# design.net
KiCad netlist of a schematic drawn in Altium Designer
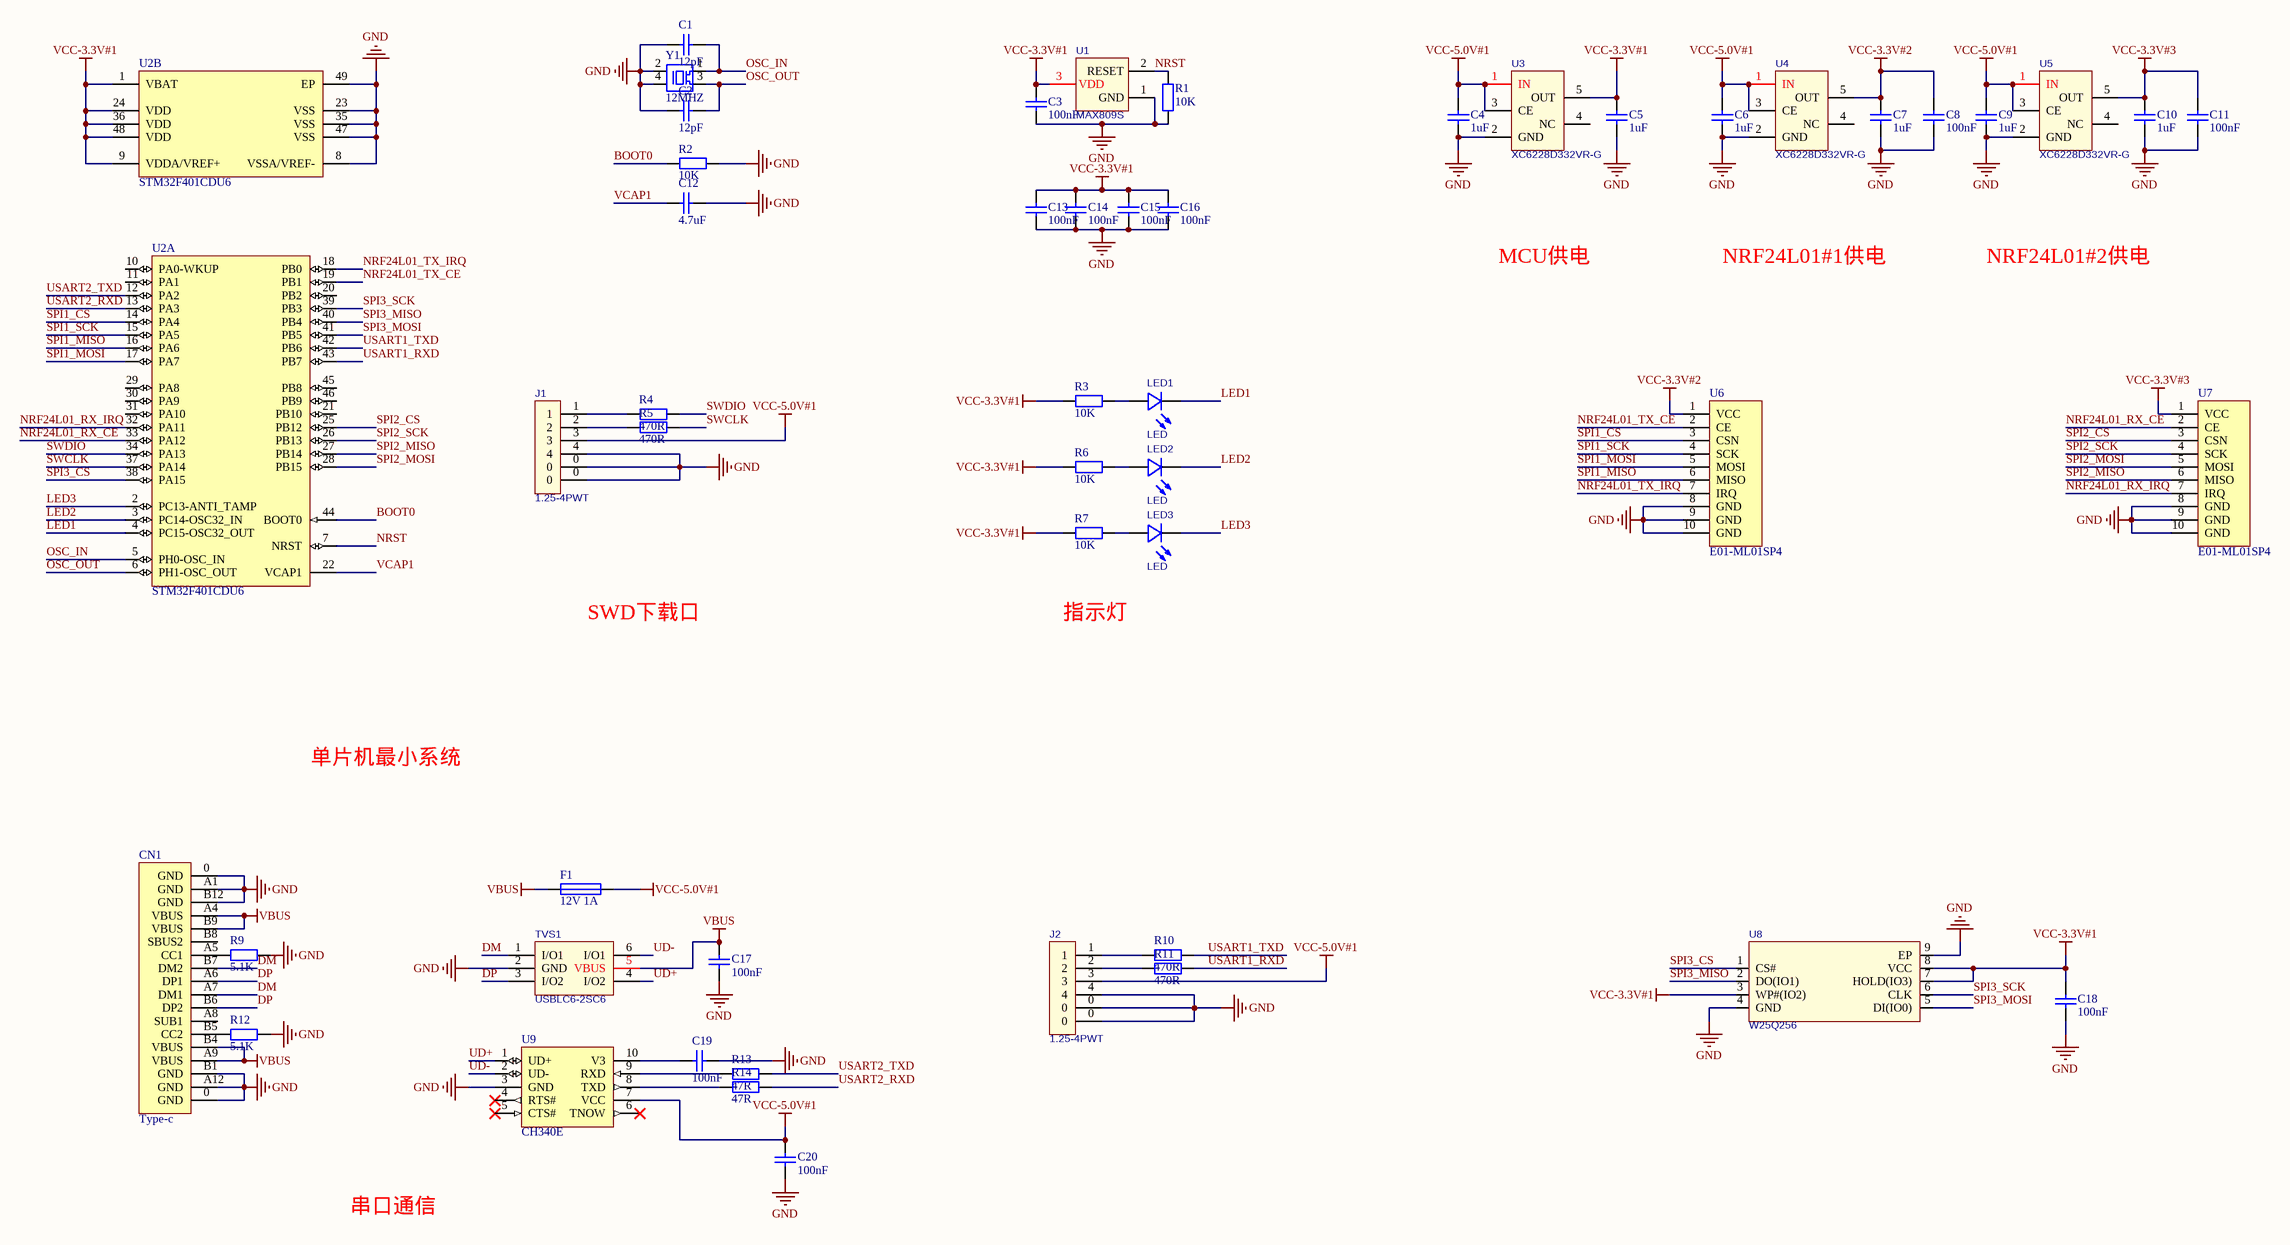
[diagram p0: 数传模块.SchDoc]

(export (version "E")
  (design (tool "Eeschema 10.0.6"))
  (components
    (comp (ref "C1")
      (value "12pF")
      (footprint "0603-C")
      (description "贴片电容")
      (libsource (lib "封装库") (part "C"))
    )
    (comp (ref "C2")
      (value "12pF")
      (footprint "0603-C")
      (description "贴片电容")
      (libsource (lib "封装库") (part "C"))
    )
    (comp (ref "C3")
      (value "100nF")
      (footprint "0603-C")
      (description "贴片电容")
      (libsource (lib "封装库") (part "C"))
    )
    (comp (ref "C4")
      (value "1uF")
      (footprint "0603-C")
      (description "贴片电容")
      (libsource (lib "封装库") (part "C"))
    )
    (comp (ref "C5")
      (value "1uF")
      (footprint "0603-C")
      (description "贴片电容")
      (libsource (lib "封装库") (part "C"))
    )
    (comp (ref "C6")
      (value "1uF")
      (footprint "0603-C")
      (description "贴片电容")
      (libsource (lib "封装库") (part "C"))
    )
    (comp (ref "C7")
      (value "1uF")
      (footprint "0603-C")
      (description "贴片电容")
      (libsource (lib "封装库") (part "C"))
    )
    (comp (ref "C8")
      (value "100nF")
      (footprint "0603-C")
      (description "贴片电容")
      (libsource (lib "封装库") (part "C"))
    )
    (comp (ref "C9")
      (value "1uF")
      (footprint "0603-C")
      (description "贴片电容")
      (libsource (lib "封装库") (part "C"))
    )
    (comp (ref "C10")
      (value "1uF")
      (footprint "0603-C")
      (description "贴片电容")
      (libsource (lib "封装库") (part "C"))
    )
    (comp (ref "C11")
      (value "100nF")
      (footprint "0603-C")
      (description "贴片电容")
      (libsource (lib "封装库") (part "C"))
    )
    (comp (ref "C12")
      (value "4.7uF")
      (footprint "0603-C")
      (description "贴片电容")
      (libsource (lib "封装库") (part "C"))
    )
    (comp (ref "C13")
      (value "100nF")
      (footprint "0603-C")
      (description "贴片电容")
      (libsource (lib "封装库") (part "C"))
    )
    (comp (ref "C14")
      (value "100nF")
      (footprint "0603-C")
      (description "贴片电容")
      (libsource (lib "封装库") (part "C"))
    )
    (comp (ref "C15")
      (value "100nF")
      (footprint "0603-C")
      (description "贴片电容")
      (libsource (lib "封装库") (part "C"))
    )
    (comp (ref "C16")
      (value "100nF")
      (footprint "0603-C")
      (description "贴片电容")
      (libsource (lib "封装库") (part "C"))
    )
    (comp (ref "C17")
      (value "100nF")
      (footprint "0603-C")
      (description "贴片电容")
      (libsource (lib "封装库") (part "C"))
    )
    (comp (ref "C18")
      (value "100nF")
      (footprint "0603-C")
      (description "贴片电容")
      (libsource (lib "封装库") (part "C"))
    )
    (comp (ref "C19")
      (value "100nF")
      (footprint "0603-C")
      (description "贴片电容")
      (libsource (lib "封装库") (part "C"))
    )
    (comp (ref "C20")
      (value "100nF")
      (footprint "0603-C")
      (description "贴片电容")
      (libsource (lib "封装库") (part "C"))
    )
    (comp (ref "CN1")
      (value "Type-c")
      (footprint "Type-c 16pin")
      (description "U262-161N-4BVC11")
      (libsource (lib "封装库") (part "Type-c"))
    )
    (comp (ref "F1")
      (value "12V 1A")
      (footprint "0805-FUSE")
      (description "12V,自恢复保险丝")
      (libsource (lib "封装库") (part "FUSE"))
    )
    (comp (ref "J1")
      (value "1.25-4PWT")
      (footprint "H1.25-4P")
      (fields (field (name "BOM_SUPPLIER PART") "C2763632") (field (name "CONTRIBUTOR") "LCSC"))
      (libsource (lib "封装库") (part "H1.25-4P"))
    )
    (comp (ref "J2")
      (value "1.25-4PWT")
      (footprint "H1.25-4P")
      (fields (field (name "BOM_SUPPLIER PART") "C2763632") (field (name "CONTRIBUTOR") "LCSC"))
      (libsource (lib "封装库") (part "H1.25-4P"))
    )
    (comp (ref "LED1")
      (value "LED")
      (footprint "LED-0603")
      (fields
        (field (name "BOM_SUPPLIER PART") "C118334")
        (field (name "BOM_MANUFACTURER PART") "D-G060306G1-KS2")
        (field (name "CONTRIBUTOR") "LCSC")
      )
      (libsource (lib "封装库") (part "LED"))
    )
    (comp (ref "LED2")
      (value "LED")
      (footprint "LED-0603")
      (fields
        (field (name "BOM_SUPPLIER PART") "C118334")
        (field (name "BOM_MANUFACTURER PART") "D-G060306G1-KS2")
        (field (name "CONTRIBUTOR") "LCSC")
      )
      (libsource (lib "封装库") (part "LED"))
    )
    (comp (ref "LED3")
      (value "LED")
      (footprint "LED-0603")
      (fields
        (field (name "BOM_SUPPLIER PART") "C118334")
        (field (name "BOM_MANUFACTURER PART") "D-G060306G1-KS2")
        (field (name "CONTRIBUTOR") "LCSC")
      )
      (libsource (lib "封装库") (part "LED"))
    )
    (comp (ref "R1")
      (value "10K")
      (footprint "0603-R")
      (description "贴片电阻")
      (libsource (lib "封装库") (part "R"))
    )
    (comp (ref "R2")
      (value "10K")
      (footprint "0603-R")
      (description "贴片电阻")
      (libsource (lib "封装库") (part "R"))
    )
    (comp (ref "R3")
      (value "10K")
      (footprint "0603-R")
      (description "贴片电阻")
      (libsource (lib "封装库") (part "R"))
    )
    (comp (ref "R4")
      (value "470R")
      (footprint "0603-R")
      (description "贴片电阻")
      (libsource (lib "封装库") (part "R"))
    )
    (comp (ref "R5")
      (value "470R")
      (footprint "0603-R")
      (description "贴片电阻")
      (libsource (lib "封装库") (part "R"))
    )
    (comp (ref "R6")
      (value "10K")
      (footprint "0603-R")
      (description "贴片电阻")
      (libsource (lib "封装库") (part "R"))
    )
    (comp (ref "R7")
      (value "10K")
      (footprint "0603-R")
      (description "贴片电阻")
      (libsource (lib "封装库") (part "R"))
    )
    (comp (ref "R9")
      (value "5.1K")
      (footprint "0603-R")
      (description "贴片电阻")
      (libsource (lib "封装库") (part "R"))
    )
    (comp (ref "R10")
      (value "470R")
      (footprint "0603-R")
      (description "贴片电阻")
      (libsource (lib "封装库") (part "R"))
    )
    (comp (ref "R11")
      (value "470R")
      (footprint "0603-R")
      (description "贴片电阻")
      (libsource (lib "封装库") (part "R"))
    )
    (comp (ref "R12")
      (value "5.1K")
      (footprint "0603-R")
      (description "贴片电阻")
      (libsource (lib "封装库") (part "R"))
    )
    (comp (ref "R13")
      (value "47R")
      (footprint "0603-R")
      (description "贴片电阻")
      (libsource (lib "封装库") (part "R"))
    )
    (comp (ref "R14")
      (value "47R")
      (footprint "0603-R")
      (description "贴片电阻")
      (libsource (lib "封装库") (part "R"))
    )
    (comp (ref "TVS1")
      (value "USBLC6-2SC6")
      (footprint "USBLC6-2")
      (description "USBLC6-2SC6_C2687116")
      (fields (field (name "BOM_SUPPLIER PART") "C2687116") (field (name "CONTRIBUTOR") "LCSC"))
      (libsource (lib "封装库") (part "USBLC6-2SC6"))
    )
    (comp (ref "U1")
      (value "MAX809S")
      (footprint "MAX809S")
      (fields (field (name "BOM_SUPPLIER PART") "C347371") (field (name "CONTRIBUTOR") "LCSC"))
      (libsource (lib "封装库") (part "MAX809S"))
    )
    (comp (ref "U2")
      (value "STM32F401CDU6")
      (footprint "STM32F401CDU6")
      (fields (field (name "MANUFACTURER") "STMicroelectronics") (field (name "PARTNUMBER") "STM32F401CCU6"))
      (libsource (lib "封装库") (part "STM32F401CDU6"))
    )
    (comp (ref "U3")
      (value "XC6228D332VR-G")
      (footprint "XC6228D332VR-G")
      (fields (field (name "BOM_SUPPLIER PART") "C69841"))
      (libsource (lib "封装库") (part "XC6228D332VR-G"))
    )
    (comp (ref "U4")
      (value "XC6228D332VR-G")
      (footprint "XC6228D332VR-G")
      (fields (field (name "BOM_SUPPLIER PART") "C69841"))
      (libsource (lib "封装库") (part "XC6228D332VR-G"))
    )
    (comp (ref "U5")
      (value "XC6228D332VR-G")
      (footprint "XC6228D332VR-G")
      (fields (field (name "BOM_SUPPLIER PART") "C69841"))
      (libsource (lib "封装库") (part "XC6228D332VR-G"))
    )
    (comp (ref "U6")
      (value "E01-ML01SP4")
      (footprint "PE01-ML01SP4")
      (description "贴片NREF24L01")
      (libsource (lib "封装库") (part "E01-ML01SP4"))
    )
    (comp (ref "U7")
      (value "E01-ML01SP4")
      (footprint "PE01-ML01SP4")
      (description "贴片NREF24L01")
      (libsource (lib "封装库") (part "E01-ML01SP4"))
    )
    (comp (ref "U8")
      (value "W25Q256")
      (footprint "W25Q256")
      (fields
        (field (name "BOM_SUPPLIER PART") "C2682312")
        (field (name "BOM_MANUFACTURER PART") "W25Q256JVEIQ")
        (field (name "CONTRIBUTOR") "LCSC")
      )
      (libsource (lib "封装库") (part "W25Q256"))
    )
    (comp (ref "U9")
      (value "CH340E")
      (footprint "CH340E")
      (description "USB to TTL Serial / UART")
      (libsource (lib "封装库") (part "CH340E"))
    )
    (comp (ref "Y1")
      (value "12MHZ")
      (footprint "3225")
      (description "无源晶振")
      (libsource (lib "封装库") (part "Y"))
    )
  )
  (nets
    (net (code "1") (name "/BOOT0") (class "Default")
      (node (ref "R2") (pin "1") (pinfunction "1_1") (pintype "passive"))
      (node (ref "U2") (pin "44") (pinfunction "BOOT0_44") (pintype "input"))
    )
    (net (code "2") (name "/DM") (class "Default")
      (node (ref "CN1") (pin "A7") (pinfunction "DM1_A7") (pintype "passive"))
      (node (ref "CN1") (pin "B7") (pinfunction "DM2_B7") (pintype "passive"))
      (node (ref "TVS1") (pin "1") (pinfunction "I/O1_1") (pintype "passive"))
    )
    (net (code "3") (name "/DP") (class "Default")
      (node (ref "CN1") (pin "A6") (pinfunction "DP1_A6") (pintype "passive"))
      (node (ref "CN1") (pin "B6") (pinfunction "DP2_B6") (pintype "passive"))
      (node (ref "TVS1") (pin "3") (pinfunction "I/O2_3") (pintype "passive"))
    )
    (net (code "4") (name "/LED1") (class "Default")
      (node (ref "LED1") (pin "1") (pinfunction "-_1") (pintype "passive"))
      (node (ref "U2") (pin "4") (pinfunction "PC15-OSC32_OUT_4") (pintype "bidirectional"))
    )
    (net (code "5") (name "/LED2") (class "Default")
      (node (ref "LED2") (pin "1") (pinfunction "-_1") (pintype "passive"))
      (node (ref "U2") (pin "3") (pinfunction "PC14-OSC32_IN_3") (pintype "bidirectional"))
    )
    (net (code "6") (name "/LED3") (class "Default")
      (node (ref "LED3") (pin "1") (pinfunction "-_1") (pintype "passive"))
      (node (ref "U2") (pin "2") (pinfunction "PC13-ANTI_TAMP_2") (pintype "bidirectional"))
    )
    (net (code "7") (name "/NRF24L01_RX_CE") (class "Default")
      (node (ref "U2") (pin "33") (pinfunction "PA12_33") (pintype "bidirectional"))
      (node (ref "U7") (pin "2") (pinfunction "CE_2") (pintype "passive"))
    )
    (net (code "8") (name "/NRF24L01_RX_IRQ") (class "Default")
      (node (ref "U2") (pin "32") (pinfunction "PA11_32") (pintype "bidirectional"))
      (node (ref "U7") (pin "7") (pinfunction "IRQ_7") (pintype "passive"))
    )
    (net (code "9") (name "/NRF24L01_TX_CE") (class "Default")
      (node (ref "U2") (pin "19") (pinfunction "PB1_19") (pintype "bidirectional"))
      (node (ref "U6") (pin "2") (pinfunction "CE_2") (pintype "passive"))
    )
    (net (code "10") (name "/NRF24L01_TX_IRQ") (class "Default")
      (node (ref "U2") (pin "18") (pinfunction "PB0_18") (pintype "bidirectional"))
      (node (ref "U6") (pin "7") (pinfunction "IRQ_7") (pintype "passive"))
    )
    (net (code "11") (name "/NRST") (class "Default")
      (node (ref "R1") (pin "2") (pinfunction "2_2") (pintype "passive"))
      (node (ref "U1") (pin "2") (pinfunction "RESET_2") (pintype "passive"))
      (node (ref "U2") (pin "7") (pinfunction "NRST_7") (pintype "bidirectional"))
    )
    (net (code "12") (name "/OSC_IN") (class "Default")
      (node (ref "C1") (pin "2") (pinfunction "2_2") (pintype "passive"))
      (node (ref "U2") (pin "5") (pinfunction "PH0-OSC_IN_5") (pintype "bidirectional"))
      (node (ref "Y1") (pin "1") (pinfunction "XTAL1_1") (pintype "passive"))
    )
    (net (code "13") (name "/OSC_OUT") (class "Default")
      (node (ref "C2") (pin "2") (pinfunction "2_2") (pintype "passive"))
      (node (ref "U2") (pin "6") (pinfunction "PH1-OSC_OUT_6") (pintype "bidirectional"))
      (node (ref "Y1") (pin "3") (pinfunction "XTAL3_3") (pintype "passive"))
    )
    (net (code "14") (name "/SPI1_CS") (class "Default")
      (node (ref "U2") (pin "14") (pinfunction "PA4_14") (pintype "bidirectional"))
      (node (ref "U6") (pin "3") (pinfunction "CSN_3") (pintype "passive"))
    )
    (net (code "15") (name "/SPI1_MISO") (class "Default")
      (node (ref "U2") (pin "16") (pinfunction "PA6_16") (pintype "bidirectional"))
      (node (ref "U6") (pin "6") (pinfunction "MISO_6") (pintype "passive"))
    )
    (net (code "16") (name "/SPI1_MOSI") (class "Default")
      (node (ref "U2") (pin "17") (pinfunction "PA7_17") (pintype "bidirectional"))
      (node (ref "U6") (pin "5") (pinfunction "MOSI_5") (pintype "passive"))
    )
    (net (code "17") (name "/SPI1_SCK") (class "Default")
      (node (ref "U2") (pin "15") (pinfunction "PA5_15") (pintype "bidirectional"))
      (node (ref "U6") (pin "4") (pinfunction "SCK_4") (pintype "passive"))
    )
    (net (code "18") (name "/SPI2_CS") (class "Default")
      (node (ref "U2") (pin "25") (pinfunction "PB12_25") (pintype "bidirectional"))
      (node (ref "U7") (pin "3") (pinfunction "CSN_3") (pintype "passive"))
    )
    (net (code "19") (name "/SPI2_MISO") (class "Default")
      (node (ref "U2") (pin "27") (pinfunction "PB14_27") (pintype "bidirectional"))
      (node (ref "U7") (pin "6") (pinfunction "MISO_6") (pintype "passive"))
    )
    (net (code "20") (name "/SPI2_MOSI") (class "Default")
      (node (ref "U2") (pin "28") (pinfunction "PB15_28") (pintype "bidirectional"))
      (node (ref "U7") (pin "5") (pinfunction "MOSI_5") (pintype "passive"))
    )
    (net (code "21") (name "/SPI2_SCK") (class "Default")
      (node (ref "U2") (pin "26") (pinfunction "PB13_26") (pintype "bidirectional"))
      (node (ref "U7") (pin "4") (pinfunction "SCK_4") (pintype "passive"))
    )
    (net (code "22") (name "/SPI3_CS") (class "Default")
      (node (ref "U2") (pin "38") (pinfunction "PA15_38") (pintype "bidirectional"))
      (node (ref "U8") (pin "1") (pinfunction "CS#_1") (pintype "passive"))
    )
    (net (code "23") (name "/SPI3_MISO") (class "Default")
      (node (ref "U2") (pin "40") (pinfunction "PB4_40") (pintype "bidirectional"))
      (node (ref "U8") (pin "2") (pinfunction "DO(IO1)_2") (pintype "passive"))
    )
    (net (code "24") (name "/SPI3_MOSI") (class "Default")
      (node (ref "U2") (pin "41") (pinfunction "PB5_41") (pintype "bidirectional"))
      (node (ref "U8") (pin "5") (pinfunction "DI(IO0)_5") (pintype "passive"))
    )
    (net (code "25") (name "/SPI3_SCK") (class "Default")
      (node (ref "U2") (pin "39") (pinfunction "PB3_39") (pintype "bidirectional"))
      (node (ref "U8") (pin "6") (pinfunction "CLK_6") (pintype "passive"))
    )
    (net (code "26") (name "/SWCLK") (class "Default")
      (node (ref "R5") (pin "2") (pinfunction "2_2") (pintype "passive"))
      (node (ref "U2") (pin "37") (pinfunction "PA14_37") (pintype "bidirectional"))
    )
    (net (code "27") (name "/SWDIO") (class "Default")
      (node (ref "R4") (pin "2") (pinfunction "2_2") (pintype "passive"))
      (node (ref "U2") (pin "34") (pinfunction "PA13_34") (pintype "bidirectional"))
    )
    (net (code "28") (name "/UD+") (class "Default")
      (node (ref "TVS1") (pin "4") (pinfunction "I/O2_4") (pintype "passive"))
      (node (ref "U9") (pin "1") (pinfunction "UD+_1") (pintype "bidirectional"))
    )
    (net (code "29") (name "/UD-") (class "Default")
      (node (ref "TVS1") (pin "6") (pinfunction "I/O1_6") (pintype "passive"))
      (node (ref "U9") (pin "2") (pinfunction "UD-_2") (pintype "bidirectional"))
    )
    (net (code "30") (name "/USART1_RXD") (class "Default")
      (node (ref "R11") (pin "2") (pinfunction "2_2") (pintype "passive"))
      (node (ref "U2") (pin "43") (pinfunction "PB7_43") (pintype "bidirectional"))
    )
    (net (code "31") (name "/USART1_TXD") (class "Default")
      (node (ref "R10") (pin "2") (pinfunction "2_2") (pintype "passive"))
      (node (ref "U2") (pin "42") (pinfunction "PB6_42") (pintype "bidirectional"))
    )
    (net (code "32") (name "/USART2_RXD") (class "Default")
      (node (ref "R14") (pin "1") (pinfunction "1_1") (pintype "passive"))
      (node (ref "U2") (pin "13") (pinfunction "PA3_13") (pintype "bidirectional"))
    )
    (net (code "33") (name "/USART2_TXD") (class "Default")
      (node (ref "R13") (pin "1") (pinfunction "1_1") (pintype "passive"))
      (node (ref "U2") (pin "12") (pinfunction "PA2_12") (pintype "bidirectional"))
    )
    (net (code "34") (name "/VCAP1") (class "Default")
      (node (ref "C12") (pin "1") (pinfunction "1_1") (pintype "passive"))
      (node (ref "U2") (pin "22") (pinfunction "VCAP1_22") (pintype "power_in"))
    )
    (net (code "35") (name "GND") (class "Default")
      (node (ref "C1") (pin "1") (pinfunction "1_1") (pintype "passive"))
      (node (ref "C10") (pin "1") (pinfunction "1_1") (pintype "passive"))
      (node (ref "C11") (pin "1") (pinfunction "1_1") (pintype "passive"))
      (node (ref "C12") (pin "2") (pinfunction "2_2") (pintype "passive"))
      (node (ref "C13") (pin "1") (pinfunction "1_1") (pintype "passive"))
      (node (ref "C14") (pin "1") (pinfunction "1_1") (pintype "passive"))
      (node (ref "C15") (pin "1") (pinfunction "1_1") (pintype "passive"))
      (node (ref "C16") (pin "1") (pinfunction "1_1") (pintype "passive"))
      (node (ref "C17") (pin "2") (pinfunction "2_2") (pintype "passive"))
      (node (ref "C18") (pin "2") (pinfunction "2_2") (pintype "passive"))
      (node (ref "C19") (pin "2") (pinfunction "2_2") (pintype "passive"))
      (node (ref "C2") (pin "1") (pinfunction "1_1") (pintype "passive"))
      (node (ref "C20") (pin "2") (pinfunction "2_2") (pintype "passive"))
      (node (ref "C3") (pin "2") (pinfunction "2_2") (pintype "passive"))
      (node (ref "C4") (pin "1") (pinfunction "1_1") (pintype "passive"))
      (node (ref "C5") (pin "1") (pinfunction "1_1") (pintype "passive"))
      (node (ref "C6") (pin "1") (pinfunction "1_1") (pintype "passive"))
      (node (ref "C7") (pin "1") (pinfunction "1_1") (pintype "passive"))
      (node (ref "C8") (pin "1") (pinfunction "1_1") (pintype "passive"))
      (node (ref "C9") (pin "1") (pinfunction "1_1") (pintype "passive"))
      (node (ref "CN1") (pin "0") (pinfunction "GND_0") (pintype "passive"))
      (node (ref "CN1") (pin "A1") (pinfunction "GND_A1") (pintype "passive"))
      (node (ref "CN1") (pin "A12") (pinfunction "GND_A12") (pintype "passive"))
      (node (ref "CN1") (pin "B1") (pinfunction "GND_B1") (pintype "passive"))
      (node (ref "CN1") (pin "B12") (pinfunction "GND_B12") (pintype "passive"))
      (node (ref "J1") (pin "0") (pinfunction "0_0") (pintype "passive"))
      (node (ref "J1") (pin "4") (pinfunction "4_4") (pintype "passive"))
      (node (ref "J2") (pin "0") (pinfunction "0_0") (pintype "passive"))
      (node (ref "J2") (pin "4") (pinfunction "4_4") (pintype "passive"))
      (node (ref "R1") (pin "1") (pinfunction "1_1") (pintype "passive"))
      (node (ref "R12") (pin "2") (pinfunction "2_2") (pintype "passive"))
      (node (ref "R2") (pin "2") (pinfunction "2_2") (pintype "passive"))
      (node (ref "R9") (pin "1") (pinfunction "1_1") (pintype "passive"))
      (node (ref "TVS1") (pin "2") (pinfunction "GND_2") (pintype "passive"))
      (node (ref "U1") (pin "1") (pinfunction "GND_1") (pintype "passive"))
      (node (ref "U2") (pin "23") (pinfunction "VSS_23") (pintype "power_in"))
      (node (ref "U2") (pin "35") (pinfunction "VSS_35") (pintype "power_in"))
      (node (ref "U2") (pin "47") (pinfunction "VSS_47") (pintype "power_in"))
      (node (ref "U2") (pin "49") (pinfunction "EP_49") (pintype "power_in"))
      (node (ref "U2") (pin "8") (pinfunction "VSSA/VREF-_8") (pintype "power_in"))
      (node (ref "U3") (pin "2") (pinfunction "GND_2") (pintype "passive"))
      (node (ref "U4") (pin "2") (pinfunction "GND_2") (pintype "passive"))
      (node (ref "U5") (pin "2") (pinfunction "GND_2") (pintype "passive"))
      (node (ref "U6") (pin "10") (pinfunction "GND_10") (pintype "passive"))
      (node (ref "U6") (pin "8") (pinfunction "GND_8") (pintype "passive"))
      (node (ref "U6") (pin "9") (pinfunction "GND_9") (pintype "passive"))
      (node (ref "U7") (pin "10") (pinfunction "GND_10") (pintype "passive"))
      (node (ref "U7") (pin "8") (pinfunction "GND_8") (pintype "passive"))
      (node (ref "U7") (pin "9") (pinfunction "GND_9") (pintype "passive"))
      (node (ref "U8") (pin "4") (pinfunction "GND_4") (pintype "passive"))
      (node (ref "U8") (pin "9") (pinfunction "EP_9") (pintype "passive"))
      (node (ref "U9") (pin "3") (pinfunction "GND_3") (pintype "power_in"))
      (node (ref "Y1") (pin "2") (pinfunction "GND_2") (pintype "passive"))
      (node (ref "Y1") (pin "4") (pinfunction "GND_4") (pintype "passive"))
    )
    (net (code "36") (name "Net-(CN1-CC1)") (class "Default")
      (node (ref "CN1") (pin "A5") (pinfunction "CC1_A5") (pintype "passive"))
      (node (ref "R9") (pin "2") (pinfunction "2_2") (pintype "passive"))
    )
    (net (code "37") (name "Net-(CN1-CC2)") (class "Default")
      (node (ref "CN1") (pin "B5") (pinfunction "CC2_B5") (pintype "passive"))
      (node (ref "R12") (pin "1") (pinfunction "1_1") (pintype "passive"))
    )
    (net (code "38") (name "Net-(J1-Pad1)") (class "Default")
      (node (ref "J1") (pin "1") (pinfunction "1_1") (pintype "passive"))
      (node (ref "R4") (pin "1") (pinfunction "1_1") (pintype "passive"))
    )
    (net (code "39") (name "Net-(J1-Pad2)") (class "Default")
      (node (ref "J1") (pin "2") (pinfunction "2_2") (pintype "passive"))
      (node (ref "R5") (pin "1") (pinfunction "1_1") (pintype "passive"))
    )
    (net (code "40") (name "Net-(J2-Pad1)") (class "Default")
      (node (ref "J2") (pin "1") (pinfunction "1_1") (pintype "passive"))
      (node (ref "R10") (pin "1") (pinfunction "1_1") (pintype "passive"))
    )
    (net (code "41") (name "Net-(J2-Pad2)") (class "Default")
      (node (ref "J2") (pin "2") (pinfunction "2_2") (pintype "passive"))
      (node (ref "R11") (pin "1") (pinfunction "1_1") (pintype "passive"))
    )
    (net (code "42") (name "Net-(LED1-+)") (class "Default")
      (node (ref "LED1") (pin "2") (pinfunction "+_2") (pintype "passive"))
      (node (ref "R3") (pin "1") (pinfunction "1_1") (pintype "passive"))
    )
    (net (code "43") (name "Net-(LED2-+)") (class "Default")
      (node (ref "LED2") (pin "2") (pinfunction "+_2") (pintype "passive"))
      (node (ref "R6") (pin "1") (pinfunction "1_1") (pintype "passive"))
    )
    (net (code "44") (name "Net-(LED3-+)") (class "Default")
      (node (ref "LED3") (pin "2") (pinfunction "+_2") (pintype "passive"))
      (node (ref "R7") (pin "1") (pinfunction "1_1") (pintype "passive"))
    )
    (net (code "45") (name "Net-(U9-RXD)") (class "Default")
      (node (ref "R13") (pin "2") (pinfunction "2_2") (pintype "passive"))
      (node (ref "U9") (pin "9") (pinfunction "RXD_9") (pintype "input"))
    )
    (net (code "46") (name "Net-(U9-TXD)") (class "Default")
      (node (ref "R14") (pin "2") (pinfunction "2_2") (pintype "passive"))
      (node (ref "U9") (pin "8") (pinfunction "TXD_8") (pintype "output"))
    )
    (net (code "47") (name "Net-(U9-V3)") (class "Default")
      (node (ref "C19") (pin "1") (pinfunction "1_1") (pintype "passive"))
      (node (ref "U9") (pin "10") (pinfunction "V3_10") (pintype "power_in"))
    )
    (net (code "48") (name "VBUS") (class "Default")
      (node (ref "C17") (pin "1") (pinfunction "1_1") (pintype "passive"))
      (node (ref "CN1") (pin "A4") (pinfunction "VBUS_A4") (pintype "passive"))
      (node (ref "CN1") (pin "A9") (pinfunction "VBUS_A9") (pintype "passive"))
      (node (ref "CN1") (pin "B4") (pinfunction "VBUS_B4") (pintype "passive"))
      (node (ref "CN1") (pin "B9") (pinfunction "VBUS_B9") (pintype "passive"))
      (node (ref "F1") (pin "2") (pinfunction "2_2") (pintype "passive"))
      (node (ref "TVS1") (pin "5") (pinfunction "VBUS_5") (pintype "passive"))
    )
    (net (code "49") (name "VCC-3.3V#1") (class "Default")
      (node (ref "C13") (pin "2") (pinfunction "2_2") (pintype "passive"))
      (node (ref "C14") (pin "2") (pinfunction "2_2") (pintype "passive"))
      (node (ref "C15") (pin "2") (pinfunction "2_2") (pintype "passive"))
      (node (ref "C16") (pin "2") (pinfunction "2_2") (pintype "passive"))
      (node (ref "C18") (pin "1") (pinfunction "1_1") (pintype "passive"))
      (node (ref "C3") (pin "1") (pinfunction "1_1") (pintype "passive"))
      (node (ref "C5") (pin "2") (pinfunction "2_2") (pintype "passive"))
      (node (ref "R3") (pin "2") (pinfunction "2_2") (pintype "passive"))
      (node (ref "R6") (pin "2") (pinfunction "2_2") (pintype "passive"))
      (node (ref "R7") (pin "2") (pinfunction "2_2") (pintype "passive"))
      (node (ref "U1") (pin "3") (pinfunction "VDD_3") (pintype "passive"))
      (node (ref "U2") (pin "1") (pinfunction "VBAT_1") (pintype "power_in"))
      (node (ref "U2") (pin "24") (pinfunction "VDD_24") (pintype "power_in"))
      (node (ref "U2") (pin "36") (pinfunction "VDD_36") (pintype "power_in"))
      (node (ref "U2") (pin "48") (pinfunction "VDD_48") (pintype "power_in"))
      (node (ref "U2") (pin "9") (pinfunction "VDDA/VREF+_9") (pintype "power_in"))
      (node (ref "U3") (pin "5") (pinfunction "OUT_5") (pintype "passive"))
      (node (ref "U8") (pin "3") (pinfunction "WP#(IO2)_3") (pintype "passive"))
      (node (ref "U8") (pin "7") (pinfunction "HOLD(IO3)_7") (pintype "passive"))
      (node (ref "U8") (pin "8") (pinfunction "VCC_8") (pintype "passive"))
    )
    (net (code "50") (name "VCC-3.3V#2") (class "Default")
      (node (ref "C7") (pin "2") (pinfunction "2_2") (pintype "passive"))
      (node (ref "C8") (pin "2") (pinfunction "2_2") (pintype "passive"))
      (node (ref "U4") (pin "5") (pinfunction "OUT_5") (pintype "passive"))
      (node (ref "U6") (pin "1") (pinfunction "VCC_1") (pintype "passive"))
    )
    (net (code "51") (name "VCC-3.3V#3") (class "Default")
      (node (ref "C10") (pin "2") (pinfunction "2_2") (pintype "passive"))
      (node (ref "C11") (pin "2") (pinfunction "2_2") (pintype "passive"))
      (node (ref "U5") (pin "5") (pinfunction "OUT_5") (pintype "passive"))
      (node (ref "U7") (pin "1") (pinfunction "VCC_1") (pintype "passive"))
    )
    (net (code "52") (name "VCC-5.0V#1") (class "Default")
      (node (ref "C20") (pin "1") (pinfunction "1_1") (pintype "passive"))
      (node (ref "C4") (pin "2") (pinfunction "2_2") (pintype "passive"))
      (node (ref "C6") (pin "2") (pinfunction "2_2") (pintype "passive"))
      (node (ref "C9") (pin "2") (pinfunction "2_2") (pintype "passive"))
      (node (ref "F1") (pin "1") (pinfunction "1_1") (pintype "passive"))
      (node (ref "J1") (pin "3") (pinfunction "3_3") (pintype "passive"))
      (node (ref "J2") (pin "3") (pinfunction "3_3") (pintype "passive"))
      (node (ref "U3") (pin "1") (pinfunction "IN_1") (pintype "passive"))
      (node (ref "U3") (pin "3") (pinfunction "CE_3") (pintype "passive"))
      (node (ref "U4") (pin "1") (pinfunction "IN_1") (pintype "passive"))
      (node (ref "U4") (pin "3") (pinfunction "CE_3") (pintype "passive"))
      (node (ref "U5") (pin "1") (pinfunction "IN_1") (pintype "passive"))
      (node (ref "U5") (pin "3") (pinfunction "CE_3") (pintype "passive"))
      (node (ref "U9") (pin "7") (pinfunction "VCC_7") (pintype "power_in"))
    )
    (net (code "53") (name "unconnected-(CN1-SBUS2-PadB8)") (class "Default")
      (node (ref "CN1") (pin "B8") (pinfunction "SBUS2_B8") (pintype "passive"))
    )
    (net (code "54") (name "unconnected-(CN1-SUB1-PadA8)") (class "Default")
      (node (ref "CN1") (pin "A8") (pinfunction "SUB1_A8") (pintype "passive"))
    )
    (net (code "55") (name "unconnected-(U2A-PA0-WKUP-Pad10)") (class "Default")
      (node (ref "U2") (pin "10") (pinfunction "PA0-WKUP_10") (pintype "bidirectional"))
    )
    (net (code "56") (name "unconnected-(U2A-PA1-Pad11)") (class "Default")
      (node (ref "U2") (pin "11") (pinfunction "PA1_11") (pintype "bidirectional"))
    )
    (net (code "57") (name "unconnected-(U2A-PA8-Pad29)") (class "Default")
      (node (ref "U2") (pin "29") (pinfunction "PA8_29") (pintype "bidirectional"))
    )
    (net (code "58") (name "unconnected-(U2A-PA9-Pad30)") (class "Default")
      (node (ref "U2") (pin "30") (pinfunction "PA9_30") (pintype "bidirectional"))
    )
    (net (code "59") (name "unconnected-(U2A-PA10-Pad31)") (class "Default")
      (node (ref "U2") (pin "31") (pinfunction "PA10_31") (pintype "bidirectional"))
    )
    (net (code "60") (name "unconnected-(U2A-PB2-Pad20)") (class "Default")
      (node (ref "U2") (pin "20") (pinfunction "PB2_20") (pintype "bidirectional"))
    )
    (net (code "61") (name "unconnected-(U2A-PB8-Pad45)") (class "Default")
      (node (ref "U2") (pin "45") (pinfunction "PB8_45") (pintype "bidirectional"))
    )
    (net (code "62") (name "unconnected-(U2A-PB9-Pad46)") (class "Default")
      (node (ref "U2") (pin "46") (pinfunction "PB9_46") (pintype "bidirectional"))
    )
    (net (code "63") (name "unconnected-(U2A-PB10-Pad21)") (class "Default")
      (node (ref "U2") (pin "21") (pinfunction "PB10_21") (pintype "bidirectional"))
    )
    (net (code "64") (name "unconnected-(U3-NC-Pad4)") (class "Default")
      (node (ref "U3") (pin "4") (pinfunction "NC_4") (pintype "passive"))
    )
    (net (code "65") (name "unconnected-(U4-NC-Pad4)") (class "Default")
      (node (ref "U4") (pin "4") (pinfunction "NC_4") (pintype "passive"))
    )
    (net (code "66") (name "unconnected-(U5-NC-Pad4)") (class "Default")
      (node (ref "U5") (pin "4") (pinfunction "NC_4") (pintype "passive"))
    )
    (net (code "67") (name "unconnected-(U9-CTS#-Pad5)") (class "Default")
      (node (ref "U9") (pin "5") (pinfunction "CTS#_5") (pintype "input+no_connect"))
    )
    (net (code "68") (name "unconnected-(U9-RTS#-Pad4)") (class "Default")
      (node (ref "U9") (pin "4") (pinfunction "RTS#_4") (pintype "output+no_connect"))
    )
    (net (code "69") (name "unconnected-(U9-TNOW-Pad6)") (class "Default")
      (node (ref "U9") (pin "6") (pinfunction "TNOW_6") (pintype "output+no_connect"))
    )
  )
)
